# 2_MicroController.net
KiCad netlist of a schematic drawn in Altium Designer
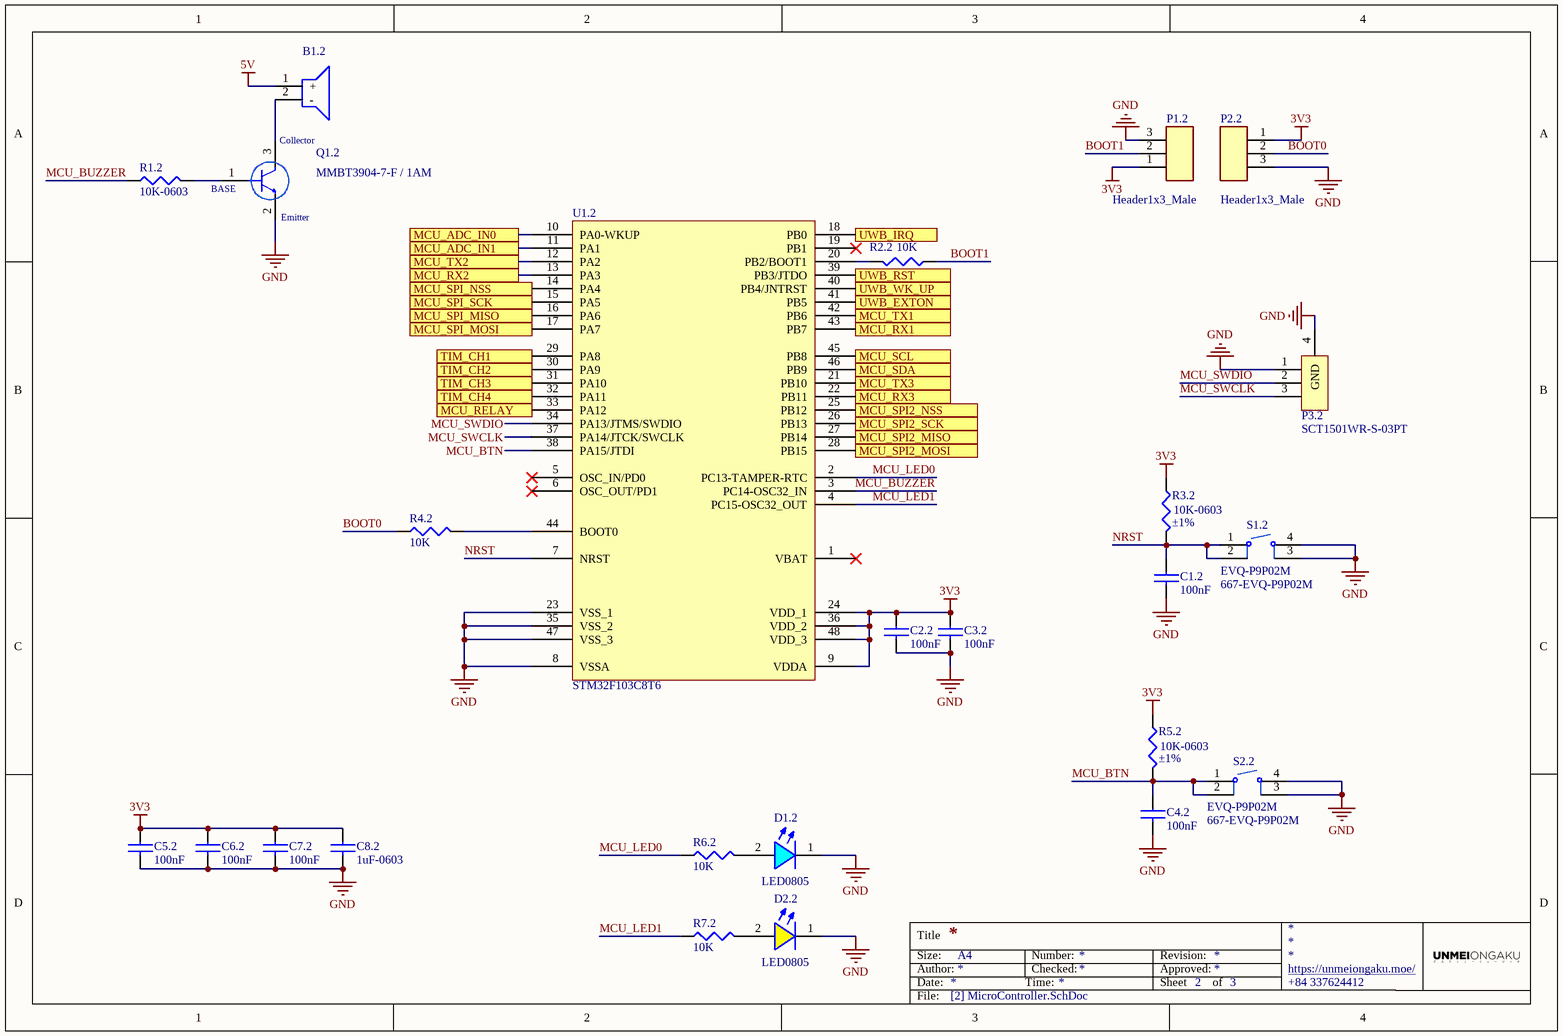
[diagram p0: [2] MicroController.SchDoc]

(export (version "E")
  (design (tool "Eeschema 10.0.6"))
  (components
    (comp (ref "B1.2")
      (value "Buzzer")
      (footprint "Buzzer 9x5mm 60dB")
      (description "9050 DIP Buzzer 9x5mm 60dB")
      (fields (field (name "LOCAL SUPPLIER PART NUMBER") "1209 DIP Buzzer 12x9mm"))
      (libsource (lib "Minh_Lib") (part "Buzzer 9050 - DIP"))
    )
    (comp (ref "C1.2")
      (value "100nF")
      (footprint "CAP0603")
      (description "CAP CER 0.1UF 50V X7R 0603")
      (fields (field (name "TOLERANCE") "±10%"))
      (libsource (lib "Minh_Lib") (part "CC0603KRX7R9BB104"))
    )
    (comp (ref "C2.2")
      (value "100nF")
      (footprint "CAP0603")
      (description "CAP CER 0.1UF 50V X7R 0603")
      (fields (field (name "TOLERANCE") "±10%"))
      (libsource (lib "Minh_Lib") (part "CC0603KRX7R9BB104"))
    )
    (comp (ref "C3.2")
      (value "100nF")
      (footprint "CAP0603")
      (description "CAP CER 0.1UF 50V X7R 0603")
      (fields (field (name "TOLERANCE") "±10%"))
      (libsource (lib "Minh_Lib") (part "CC0603KRX7R9BB104"))
    )
    (comp (ref "C4.2")
      (value "100nF")
      (footprint "CAP0603")
      (description "CAP CER 0.1UF 50V X7R 0603")
      (fields (field (name "TOLERANCE") "±10%"))
      (libsource (lib "Minh_Lib") (part "CC0603KRX7R9BB104"))
    )
    (comp (ref "C5.2")
      (value "100nF")
      (footprint "CAP0603")
      (description "CAP CER 0.1UF 50V X7R 0603")
      (fields (field (name "TOLERANCE") "±10%"))
      (libsource (lib "Minh_Lib") (part "CC0603KRX7R9BB104"))
    )
    (comp (ref "C6.2")
      (value "100nF")
      (footprint "CAP0603")
      (description "CAP CER 0.1UF 50V X7R 0603")
      (fields (field (name "TOLERANCE") "±10%"))
      (libsource (lib "Minh_Lib") (part "CC0603KRX7R9BB104"))
    )
    (comp (ref "C7.2")
      (value "100nF")
      (footprint "CAP0603")
      (description "CAP CER 0.1UF 50V X7R 0603")
      (fields (field (name "TOLERANCE") "±10%"))
      (libsource (lib "Minh_Lib") (part "CC0603KRX7R9BB104"))
    )
    (comp (ref "C8.2")
      (value "1uF-0603")
      (footprint "CAP0603")
      (description "CAP CER 1UF 16V X7R 0603")
      (fields (field (name "TOLERANCE") "±10%"))
      (libsource (lib "Minh_Lib") (part "CC0603KRX7R7BB105"))
    )
    (comp (ref "D1.2")
      (value "LED0805")
      (footprint "LED0805-BLUE")
      (libsource (lib "Minh_Lib") (part "LED0805-BLUE"))
    )
    (comp (ref "D2.2")
      (value "LED0805")
      (footprint "LED0805-YELLOW")
      (libsource (lib "Minh_Lib") (part "LED0805-YELLOW"))
    )
    (comp (ref "P1.2")
      (value "Header1x3_Male")
      (footprint "Minh_Lib:HDR1x3_2.54_MALE")
      (description "Header1x3_2.54_MALE")
      (libsource (lib "Minh_Lib") (part "HDR1x3_2.54_MALE"))
    )
    (comp (ref "P2.2")
      (value "Header1x3_Male")
      (footprint "Minh_Lib:HDR1x3_2.54_MALE")
      (description "Header1x3_2.54_MALE")
      (libsource (lib "") (part "HDR1x3_2.54_MALE_1"))
    )
    (comp (ref "P3.2")
      (value "SCT1501WR-S-03PT")
      (footprint "Connector ZH1.5 3P SMD")
      (libsource (lib "Minh_Lib") (part "SCT1501WR-S-03PT"))
    )
    (comp (ref "Q1.2")
      (value "MMBT3904-7-F / 1AM")
      (footprint "SOT23")
      (description "Transistor General Purpose BJT NPN 40 Volt 0.2A Automotive 3-Pin SOT-23")
      (fields
        (field (name "MANUFACTURER") "Diodes Zetex")
        (field (name "MANUFACTURER PART NUMBER") "MMBT3904-7-F")
      )
      (libsource (lib "Minh_Lib") (part "MMBT3904-7-F / 1AM"))
    )
    (comp (ref "R1.2")
      (value "10K-0603")
      (footprint "RES0603 - 3D")
      (description "RES SMD 10K OHM 5% 1/10W 0603")
      (fields (field (name "TOLERANCE") "±5%"))
      (libsource (lib "Minh_Lib") (part "RC0603JR-0710KL"))
    )
    (comp (ref "R2.2")
      (value "10K")
      (footprint "RES0603 - 3D")
      (description "RES SMD 10K OHM 1% 1/10W 0603")
      (fields
        (field (name "MANUFACTURER") "Yageo")
        (field (name "MANUFACTURER PART NUMBER") "RC0603FR-0710KL")
      )
      (libsource (lib "Minh_Lib") (part "RC0603FR-0710KL"))
    )
    (comp (ref "R3.2")
      (value "10K-0603")
      (footprint "RES0603 - 3D")
      (description "RES SMD 10K OHM 1% 1/10W 0603")
      (fields
        (field (name "MANUFACTURER") "Yageo")
        (field (name "MANUFACTURER PART NUMBER") "RC0603FR-0710KL")
        (field (name "TOLERANCE") "±1%")
      )
      (libsource (lib "Minh_Lib") (part "RC0603FR-0710KL"))
    )
    (comp (ref "R4.2")
      (value "10K")
      (footprint "RES0603 - 3D")
      (description "RES SMD 10K OHM 1% 1/10W 0603")
      (fields
        (field (name "MANUFACTURER") "Yageo")
        (field (name "MANUFACTURER PART NUMBER") "RC0603FR-0710KL")
      )
      (libsource (lib "Minh_Lib") (part "RC0603FR-0710KL"))
    )
    (comp (ref "R5.2")
      (value "10K-0603")
      (footprint "RES0603 - 3D")
      (description "RES SMD 10K OHM 1% 1/10W 0603")
      (fields
        (field (name "MANUFACTURER") "Yageo")
        (field (name "MANUFACTURER PART NUMBER") "RC0603FR-0710KL")
        (field (name "TOLERANCE") "±1%")
      )
      (libsource (lib "Minh_Lib") (part "RC0603FR-0710KL"))
    )
    (comp (ref "R6.2")
      (value "10K")
      (footprint "RES0603 - 3D")
      (description "RES SMD 10K OHM 1% 1/10W 0603")
      (fields
        (field (name "MANUFACTURER") "Yageo")
        (field (name "MANUFACTURER PART NUMBER") "RC0603FR-0710KL")
      )
      (libsource (lib "Minh_Lib") (part "RC0603FR-0710KL"))
    )
    (comp (ref "R7.2")
      (value "10K")
      (footprint "RES0603 - 3D")
      (description "RES SMD 10K OHM 1% 1/10W 0603")
      (fields
        (field (name "MANUFACTURER") "Yageo")
        (field (name "MANUFACTURER PART NUMBER") "RC0603FR-0710KL")
      )
      (libsource (lib "Minh_Lib") (part "RC0603FR-0710KL"))
    )
    (comp (ref "S1.2")
      (value "EVQ-P9P02M")
      (footprint "TactileSwitch,SMT,4.2x3.2x2.5mm,4N")
      (description "Switch Tactile N.O. SPST Rectangular Button J-Bend 0.02A 15VDC 5N SMD Embossed Tape and Reel")
      (fields
        (field (name "MANUFACTURER") "Panasonic")
        (field (name "SUPPLIER PART NUMBER 1") "667-EVQ-P9P02M")
      )
      (libsource (lib "Minh_Lib") (part "EVQ-P9P02M"))
    )
    (comp (ref "S2.2")
      (value "EVQ-P9P02M")
      (footprint "TactileSwitch,SMT,4.2x3.2x2.5mm,4N")
      (description "Switch Tactile N.O. SPST Rectangular Button J-Bend 0.02A 15VDC 5N SMD Embossed Tape and Reel")
      (fields
        (field (name "MANUFACTURER") "Panasonic")
        (field (name "SUPPLIER PART NUMBER 1") "667-EVQ-P9P02M")
      )
      (libsource (lib "Minh_Lib") (part "EVQ-P9P02M"))
    )
    (comp (ref "U1.2")
      (value "STM32F103C8T6")
      (footprint "Minh_Lib:LQFP48_L")
      (description "STM32 ARM-based 32-bit MCU with 64 Kbytes Flash, 48-pin LQFP, Industrial Temperature")
      (fields (field (name "PUBLISHER") "Altium Limited"))
      (libsource (lib "Minh_Lib") (part "STM32F103C8T6"))
    )
  )
  (nets
    (net (code "1") (name "/BOOT0") (class "Default")
      (node (ref "P2.2") (pin "2") (pinfunction "2_2") (pintype "passive"))
      (node (ref "R4.2") (pin "1") (pinfunction "1_1") (pintype "passive"))
    )
    (net (code "2") (name "/BOOT1") (class "Default")
      (node (ref "P1.2") (pin "2") (pinfunction "2_2") (pintype "passive"))
      (node (ref "R2.2") (pin "1") (pinfunction "1_1") (pintype "passive"))
    )
    (net (code "3") (name "/MCU_ADC_IN0") (class "Default")
      (node (ref "U1.2") (pin "10") (pinfunction "PA0-WKUP_10") (pintype "passive"))
    )
    (net (code "4") (name "/MCU_ADC_IN1") (class "Default")
      (node (ref "U1.2") (pin "11") (pinfunction "PA1_11") (pintype "passive"))
    )
    (net (code "5") (name "/MCU_BTN") (class "Default")
      (node (ref "C4.2") (pin "1") (pinfunction "1_1") (pintype "passive"))
      (node (ref "R5.2") (pin "2") (pinfunction "2_2") (pintype "passive"))
      (node (ref "S2.2") (pin "1") (pintype "passive"))
      (node (ref "S2.2") (pin "2") (pintype "passive"))
      (node (ref "U1.2") (pin "38") (pinfunction "PA15/JTDI_38") (pintype "passive"))
    )
    (net (code "6") (name "/MCU_BUZZER") (class "Default")
      (node (ref "R1.2") (pin "1") (pinfunction "1_1") (pintype "passive"))
      (node (ref "U1.2") (pin "3") (pinfunction "PC14-OSC32_IN_3") (pintype "passive"))
    )
    (net (code "7") (name "/MCU_LED0") (class "Default")
      (node (ref "R6.2") (pin "1") (pinfunction "1_1") (pintype "passive"))
      (node (ref "U1.2") (pin "2") (pinfunction "PC13-TAMPER-RTC_2") (pintype "passive"))
    )
    (net (code "8") (name "/MCU_LED1") (class "Default")
      (node (ref "R7.2") (pin "1") (pinfunction "1_1") (pintype "passive"))
      (node (ref "U1.2") (pin "4") (pinfunction "PC15-OSC32_OUT_4") (pintype "passive"))
    )
    (net (code "9") (name "/MCU_RELAY") (class "Default")
      (node (ref "U1.2") (pin "33") (pinfunction "PA12_33") (pintype "passive"))
    )
    (net (code "11") (name "/MCU_RX1") (class "Default")
      (node (ref "U1.2") (pin "43") (pinfunction "PB7_43") (pintype "passive"))
    )
    (net (code "19") (name "/MCU_RX2") (class "Default")
      (node (ref "U1.2") (pin "13") (pinfunction "PA3_13") (pintype "passive"))
    )
    (net (code "20") (name "/MCU_RX3") (class "Default")
      (node (ref "U1.2") (pin "22") (pinfunction "PB11_22") (pintype "passive"))
    )
    (net (code "21") (name "/MCU_SCL") (class "Default")
      (node (ref "U1.2") (pin "45") (pinfunction "PB8_45") (pintype "passive"))
    )
    (net (code "22") (name "/MCU_SDA") (class "Default")
      (node (ref "U1.2") (pin "46") (pinfunction "PB9_46") (pintype "passive"))
    )
    (net (code "23") (name "/MCU_SPI2_MISO") (class "Default")
      (node (ref "U1.2") (pin "27") (pinfunction "PB14_27") (pintype "passive"))
    )
    (net (code "24") (name "/MCU_SPI2_MOSI") (class "Default")
      (node (ref "U1.2") (pin "28") (pinfunction "PB15_28") (pintype "passive"))
    )
    (net (code "26") (name "/MCU_SPI2_NSS") (class "Default")
      (node (ref "U1.2") (pin "25") (pinfunction "PB12_25") (pintype "passive"))
    )
    (net (code "28") (name "/MCU_SPI2_SCK") (class "Default")
      (node (ref "U1.2") (pin "26") (pinfunction "PB13_26") (pintype "passive"))
    )
    (net (code "29") (name "/MCU_SPI_MISO") (class "Default")
      (node (ref "U1.2") (pin "16") (pinfunction "PA6_16") (pintype "passive"))
    )
    (net (code "30") (name "/MCU_SPI_MOSI") (class "Default")
      (node (ref "U1.2") (pin "17") (pinfunction "PA7_17") (pintype "passive"))
    )
    (net (code "31") (name "/MCU_SPI_NSS") (class "Default")
      (node (ref "U1.2") (pin "14") (pinfunction "PA4_14") (pintype "passive"))
    )
    (net (code "32") (name "/MCU_SPI_SCK") (class "Default")
      (node (ref "U1.2") (pin "15") (pinfunction "PA5_15") (pintype "passive"))
    )
    (net (code "37") (name "/MCU_SWCLK") (class "Default")
      (node (ref "P3.2") (pin "3") (pinfunction "3_3") (pintype "passive"))
      (node (ref "U1.2") (pin "37") (pinfunction "PA14/JTCK/SWCLK_37") (pintype "passive"))
    )
    (net (code "38") (name "/MCU_SWDIO") (class "Default")
      (node (ref "P3.2") (pin "2") (pinfunction "2_2") (pintype "passive"))
      (node (ref "U1.2") (pin "34") (pinfunction "PA13/JTMS/SWDIO_34") (pintype "passive"))
    )
    (net (code "39") (name "/MCU_TX1") (class "Default")
      (node (ref "U1.2") (pin "42") (pinfunction "PB6_42") (pintype "passive"))
    )
    (net (code "40") (name "/MCU_TX2") (class "Default")
      (node (ref "U1.2") (pin "12") (pinfunction "PA2_12") (pintype "passive"))
    )
    (net (code "41") (name "/MCU_TX3") (class "Default")
      (node (ref "U1.2") (pin "21") (pinfunction "PB10_21") (pintype "passive"))
    )
    (net (code "42") (name "/NRST") (class "Default")
      (node (ref "C1.2") (pin "1") (pinfunction "1_1") (pintype "passive"))
      (node (ref "R3.2") (pin "2") (pinfunction "2_2") (pintype "passive"))
      (node (ref "S1.2") (pin "1") (pintype "passive"))
      (node (ref "S1.2") (pin "2") (pintype "passive"))
      (node (ref "U1.2") (pin "7") (pinfunction "NRST_7") (pintype "passive"))
    )
    (net (code "43") (name "/TIM_CH1") (class "Default")
      (node (ref "U1.2") (pin "29") (pinfunction "PA8_29") (pintype "passive"))
    )
    (net (code "44") (name "/TIM_CH2") (class "Default")
      (node (ref "U1.2") (pin "30") (pinfunction "PA9_30") (pintype "passive"))
    )
    (net (code "45") (name "/TIM_CH3") (class "Default")
      (node (ref "U1.2") (pin "31") (pinfunction "PA10_31") (pintype "passive"))
    )
    (net (code "46") (name "/TIM_CH4") (class "Default")
      (node (ref "U1.2") (pin "32") (pinfunction "PA11_32") (pintype "passive"))
    )
    (net (code "47") (name "/UWB_EXTON") (class "Default")
      (node (ref "U1.2") (pin "41") (pinfunction "PB5_41") (pintype "passive"))
    )
    (net (code "48") (name "/UWB_IRQ") (class "Default")
      (node (ref "U1.2") (pin "18") (pinfunction "PB0_18") (pintype "passive"))
    )
    (net (code "49") (name "/UWB_RST") (class "Default")
      (node (ref "U1.2") (pin "39") (pinfunction "PB3/JTDO_39") (pintype "passive"))
    )
    (net (code "50") (name "/UWB_WK_UP") (class "Default")
      (node (ref "U1.2") (pin "40") (pinfunction "PB4/JNTRST_40") (pintype "passive"))
    )
    (net (code "51") (name "3V3") (class "Default")
      (node (ref "C2.2") (pin "1") (pinfunction "1_1") (pintype "passive"))
      (node (ref "C3.2") (pin "1") (pinfunction "1_1") (pintype "passive"))
      (node (ref "C5.2") (pin "1") (pinfunction "1_1") (pintype "passive"))
      (node (ref "C6.2") (pin "1") (pinfunction "1_1") (pintype "passive"))
      (node (ref "C7.2") (pin "1") (pinfunction "1_1") (pintype "passive"))
      (node (ref "C8.2") (pin "1") (pinfunction "1_1") (pintype "passive"))
      (node (ref "P1.2") (pin "1") (pinfunction "1_1") (pintype "passive"))
      (node (ref "P2.2") (pin "1") (pinfunction "1_1") (pintype "passive"))
      (node (ref "R3.2") (pin "1") (pinfunction "1_1") (pintype "passive"))
      (node (ref "R5.2") (pin "1") (pinfunction "1_1") (pintype "passive"))
      (node (ref "U1.2") (pin "24") (pinfunction "VDD_1_24") (pintype "power_in"))
      (node (ref "U1.2") (pin "36") (pinfunction "VDD_2_36") (pintype "power_in"))
      (node (ref "U1.2") (pin "48") (pinfunction "VDD_3_48") (pintype "power_in"))
      (node (ref "U1.2") (pin "9") (pinfunction "VDDA_9") (pintype "power_in"))
    )
    (net (code "52") (name "5V") (class "Default")
      (node (ref "B1.2") (pin "1") (pinfunction "+_1") (pintype "passive"))
    )
    (net (code "53") (name "GND") (class "Default")
      (node (ref "C1.2") (pin "2") (pinfunction "2_2") (pintype "passive"))
      (node (ref "C2.2") (pin "2") (pinfunction "2_2") (pintype "passive"))
      (node (ref "C3.2") (pin "2") (pinfunction "2_2") (pintype "passive"))
      (node (ref "C4.2") (pin "2") (pinfunction "2_2") (pintype "passive"))
      (node (ref "C5.2") (pin "2") (pinfunction "2_2") (pintype "passive"))
      (node (ref "C6.2") (pin "2") (pinfunction "2_2") (pintype "passive"))
      (node (ref "C7.2") (pin "2") (pinfunction "2_2") (pintype "passive"))
      (node (ref "C8.2") (pin "2") (pinfunction "2_2") (pintype "passive"))
      (node (ref "D1.2") (pin "1") (pinfunction "+_1") (pintype "passive"))
      (node (ref "D2.2") (pin "1") (pinfunction "+_1") (pintype "passive"))
      (node (ref "P1.2") (pin "3") (pinfunction "3_3") (pintype "passive"))
      (node (ref "P2.2") (pin "3") (pinfunction "3_3") (pintype "passive"))
      (node (ref "P3.2") (pin "1") (pinfunction "1_1") (pintype "passive"))
      (node (ref "P3.2") (pin "4") (pinfunction "GND_4") (pintype "passive"))
      (node (ref "Q1.2") (pin "2") (pinfunction "2_2") (pintype "passive"))
      (node (ref "S1.2") (pin "3") (pintype "passive"))
      (node (ref "S1.2") (pin "4") (pintype "passive"))
      (node (ref "S2.2") (pin "3") (pintype "passive"))
      (node (ref "S2.2") (pin "4") (pintype "passive"))
      (node (ref "U1.2") (pin "23") (pinfunction "VSS_1_23") (pintype "power_in"))
      (node (ref "U1.2") (pin "35") (pinfunction "VSS_2_35") (pintype "power_in"))
      (node (ref "U1.2") (pin "47") (pinfunction "VSS_3_47") (pintype "power_in"))
      (node (ref "U1.2") (pin "8") (pinfunction "VSSA_8") (pintype "power_in"))
    )
    (net (code "54") (name "Net-(B1.2--)") (class "Default")
      (node (ref "B1.2") (pin "2") (pinfunction "-_2") (pintype "passive"))
      (node (ref "Q1.2") (pin "3") (pinfunction "3_3") (pintype "passive"))
    )
    (net (code "55") (name "Net-(D1.2-+-Pad2)") (class "Default")
      (node (ref "D1.2") (pin "2") (pinfunction "+_2") (pintype "passive"))
      (node (ref "R6.2") (pin "2") (pinfunction "2_2") (pintype "passive"))
    )
    (net (code "56") (name "Net-(D2.2-+-Pad2)") (class "Default")
      (node (ref "D2.2") (pin "2") (pinfunction "+_2") (pintype "passive"))
      (node (ref "R7.2") (pin "2") (pinfunction "2_2") (pintype "passive"))
    )
    (net (code "57") (name "Net-(Q1.2-Pad1)") (class "Default")
      (node (ref "Q1.2") (pin "1") (pinfunction "1_1") (pintype "passive"))
      (node (ref "R1.2") (pin "2") (pinfunction "2_2") (pintype "passive"))
    )
    (net (code "58") (name "Net-(U1.2-BOOT0)") (class "Default")
      (node (ref "R4.2") (pin "2") (pinfunction "2_2") (pintype "passive"))
      (node (ref "U1.2") (pin "44") (pinfunction "BOOT0_44") (pintype "passive"))
    )
    (net (code "59") (name "Net-(U1.2-PB2{slash}BOOT1)") (class "Default")
      (node (ref "R2.2") (pin "2") (pinfunction "2_2") (pintype "passive"))
      (node (ref "U1.2") (pin "20") (pinfunction "PB2/BOOT1_20") (pintype "passive"))
    )
    (net (code "60") (name "unconnected-(U1.2-OSC_IN{slash}PD0-Pad5)") (class "Default")
      (node (ref "U1.2") (pin "5") (pinfunction "OSC_IN/PD0_5") (pintype "passive+no_connect"))
    )
    (net (code "61") (name "unconnected-(U1.2-OSC_OUT{slash}PD1-Pad6)") (class "Default")
      (node (ref "U1.2") (pin "6") (pinfunction "OSC_OUT/PD1_6") (pintype "passive+no_connect"))
    )
    (net (code "62") (name "unconnected-(U1.2-PB1-Pad19)") (class "Default")
      (node (ref "U1.2") (pin "19") (pinfunction "PB1_19") (pintype "passive+no_connect"))
    )
    (net (code "63") (name "unconnected-(U1.2-VBAT-Pad1)") (class "Default")
      (node (ref "U1.2") (pin "1") (pinfunction "VBAT_1") (pintype "power_in+no_connect"))
    )
  )
)
